# prog.net
KiCad netlist of a schematic drawn in EAGLE
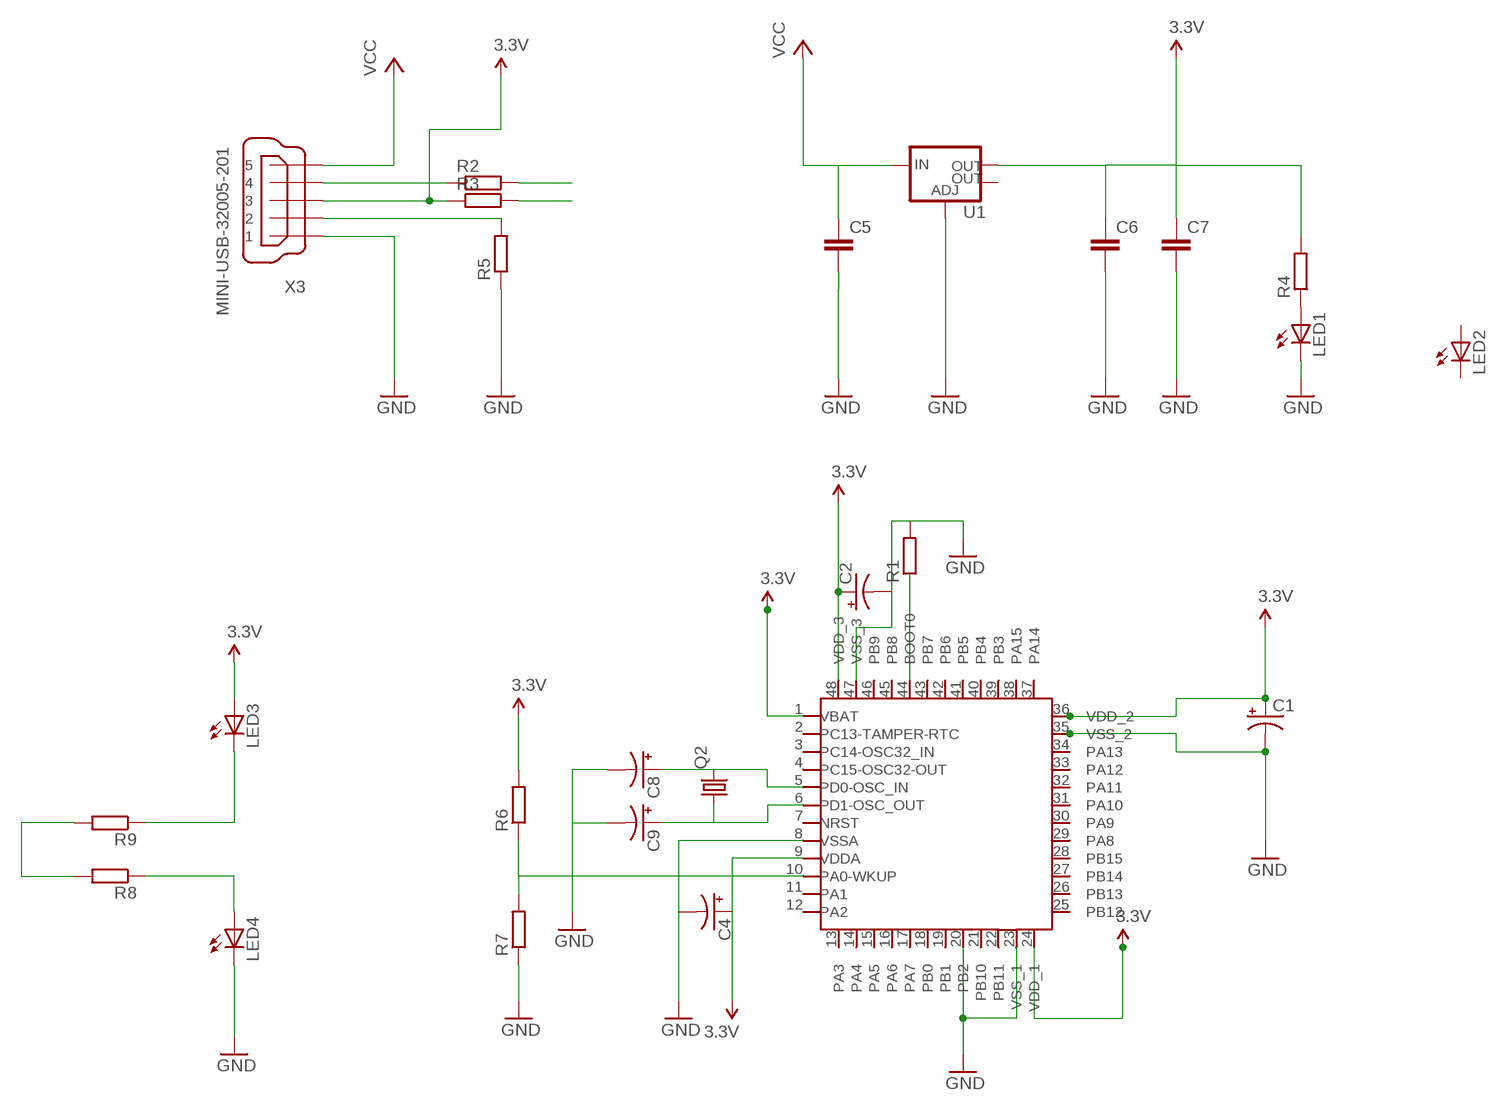
[diagram p0: schematic, sheet 1]

(export (version "E")
  (design (tool "Eeschema 10.0.6"))
  (components
    (comp (ref "C1")
      (value "POLARIZED_CAPACITORA3216-18")
      (footprint "eagle-import:A3216-18")
      (libsource (lib "eagle-import") (part "POLARIZED_CAPACITORA3216-18"))
    )
    (comp (ref "C2")
      (value "POLARIZED_CAPACITORA3216-18")
      (footprint "eagle-import:A3216-18")
      (libsource (lib "eagle-import") (part "POLARIZED_CAPACITORA3216-18"))
    )
    (comp (ref "C4")
      (value "POLARIZED_CAPACITORA3216-18")
      (footprint "eagle-import:A3216-18")
      (libsource (lib "eagle-import") (part "POLARIZED_CAPACITORA3216-18"))
    )
    (comp (ref "C5") (value "C") (footprint "eagle-import:C0805") (libsource (lib "eagle-import") (part "C")))
    (comp (ref "C6") (value "C") (footprint "eagle-import:C0805") (libsource (lib "eagle-import") (part "C")))
    (comp (ref "C7") (value "C") (footprint "eagle-import:C0805") (libsource (lib "eagle-import") (part "C")))
    (comp (ref "C8")
      (value "POLARIZED_CAPACITORA3216-18")
      (footprint "eagle-import:A3216-18")
      (libsource (lib "eagle-import") (part "POLARIZED_CAPACITORA3216-18"))
    )
    (comp (ref "C9")
      (value "POLARIZED_CAPACITORA3216-18")
      (footprint "eagle-import:A3216-18")
      (libsource (lib "eagle-import") (part "POLARIZED_CAPACITORA3216-18"))
    )
    (comp (ref "LED1")
      (value "LEDCHIP-LED0805")
      (footprint "eagle-import:CHIP-LED0805")
      (libsource (lib "eagle-import") (part "LEDCHIP-LED0805"))
    )
    (comp (ref "LED2")
      (value "LEDCHIP-LED0805")
      (footprint "eagle-import:CHIP-LED0805")
      (libsource (lib "eagle-import") (part "LEDCHIP-LED0805"))
    )
    (comp (ref "LED3")
      (value "LEDCHIP-LED0805")
      (footprint "eagle-import:CHIP-LED0805")
      (libsource (lib "eagle-import") (part "LEDCHIP-LED0805"))
    )
    (comp (ref "LED4")
      (value "LEDCHIP-LED0805")
      (footprint "eagle-import:CHIP-LED0805")
      (libsource (lib "eagle-import") (part "LEDCHIP-LED0805"))
    )
    (comp (ref "Q2")
      (value "CRYSTALSM49")
      (footprint "eagle-import:SM49")
      (libsource (lib "eagle-import") (part "CRYSTALSM49"))
    )
    (comp (ref "R1") (value "R") (footprint "eagle-import:R0805") (libsource (lib "eagle-import") (part "R")))
    (comp (ref "R2") (value "R") (footprint "eagle-import:R0805") (libsource (lib "eagle-import") (part "R")))
    (comp (ref "R3") (value "R") (footprint "eagle-import:R0805") (libsource (lib "eagle-import") (part "R")))
    (comp (ref "R4") (value "R") (footprint "eagle-import:R0805") (libsource (lib "eagle-import") (part "R")))
    (comp (ref "R5") (value "R") (footprint "eagle-import:R0805") (libsource (lib "eagle-import") (part "R")))
    (comp (ref "R6") (value "R") (footprint "eagle-import:R0805") (libsource (lib "eagle-import") (part "R")))
    (comp (ref "R7") (value "R") (footprint "eagle-import:R0805") (libsource (lib "eagle-import") (part "R")))
    (comp (ref "R8") (value "R") (footprint "eagle-import:R0805") (libsource (lib "eagle-import") (part "R")))
    (comp (ref "R9") (value "R") (footprint "eagle-import:R0805") (libsource (lib "eagle-import") (part "R")))
    (comp (ref "U$1")
      (value "STM32F103_TQFP48_7X7")
      (footprint "eagle-import:LQFP48_7X7")
      (libsource (lib "eagle-import") (part "STM32F103_TQFP48_7X7"))
    )
    (comp (ref "U1")
      (value "V_REG_LM1117SOT223")
      (footprint "eagle-import:SOT223")
      (libsource (lib "eagle-import") (part "V_REG_LM1117SOT223"))
    )
    (comp (ref "X3")
      (value "MINI-USB-32005-201")
      (footprint "eagle-import:32005-201")
      (libsource (lib "eagle-import") (part "MINI-USB-32005-201"))
    )
  )
  (nets
    (net (code "1") (name "3.3V") (class "Default")
      (node (ref "C1") (pin "+") (pinfunction "+_+") (pintype "passive"))
      (node (ref "C2") (pin "+") (pinfunction "+_+") (pintype "passive"))
      (node (ref "C4") (pin "+") (pinfunction "+_+") (pintype "passive"))
      (node (ref "C6") (pin "1") (pinfunction "1_1") (pintype "passive"))
      (node (ref "C7") (pin "1") (pinfunction "1_1") (pintype "passive"))
      (node (ref "LED3") (pin "A") (pinfunction "A_A") (pintype "passive"))
      (node (ref "R3") (pin "1") (pinfunction "1_1") (pintype "passive"))
      (node (ref "R4") (pin "2") (pinfunction "2_2") (pintype "passive"))
      (node (ref "R6") (pin "2") (pinfunction "2_2") (pintype "passive"))
      (node (ref "U$1") (pin "1") (pinfunction "VBAT_1") (pintype "bidirectional"))
      (node (ref "U$1") (pin "24") (pinfunction "VDD_1_24") (pintype "bidirectional"))
      (node (ref "U$1") (pin "36") (pinfunction "VDD_2_36") (pintype "bidirectional"))
      (node (ref "U$1") (pin "48") (pinfunction "VDD_3_48") (pintype "bidirectional"))
      (node (ref "U$1") (pin "9") (pinfunction "VDDA_9") (pintype "bidirectional"))
      (node (ref "U1") (pin "2") (pinfunction "OUT_2") (pintype "output"))
      (node (ref "X3") (pin "3") (pinfunction "3_3") (pintype "passive"))
    )
    (net (code "2") (name "GND") (class "Default")
      (node (ref "C1") (pin "-") (pinfunction "-_-") (pintype "passive"))
      (node (ref "C2") (pin "-") (pinfunction "-_-") (pintype "passive"))
      (node (ref "C4") (pin "-") (pinfunction "-_-") (pintype "passive"))
      (node (ref "C5") (pin "2") (pinfunction "2_2") (pintype "passive"))
      (node (ref "C6") (pin "2") (pinfunction "2_2") (pintype "passive"))
      (node (ref "C7") (pin "2") (pinfunction "2_2") (pintype "passive"))
      (node (ref "C8") (pin "-") (pinfunction "-_-") (pintype "passive"))
      (node (ref "C9") (pin "-") (pinfunction "-_-") (pintype "passive"))
      (node (ref "LED1") (pin "C") (pinfunction "C_C") (pintype "passive"))
      (node (ref "LED4") (pin "C") (pinfunction "C_C") (pintype "passive"))
      (node (ref "R1") (pin "2") (pinfunction "2_2") (pintype "passive"))
      (node (ref "R5") (pin "1") (pinfunction "1_1") (pintype "passive"))
      (node (ref "R7") (pin "1") (pinfunction "1_1") (pintype "passive"))
      (node (ref "U$1") (pin "20") (pinfunction "PB2_20") (pintype "bidirectional"))
      (node (ref "U$1") (pin "23") (pinfunction "VSS_1_23") (pintype "bidirectional"))
      (node (ref "U$1") (pin "35") (pinfunction "VSS_2_35") (pintype "bidirectional"))
      (node (ref "U$1") (pin "47") (pinfunction "VSS_3_47") (pintype "bidirectional"))
      (node (ref "U$1") (pin "8") (pinfunction "VSSA_8") (pintype "bidirectional"))
      (node (ref "U1") (pin "1") (pinfunction "ADJ_1") (pintype "input"))
      (node (ref "X3") (pin "1") (pinfunction "1_1") (pintype "passive"))
    )
    (net (code "3") (name "Net-(LED1-PadA)") (class "Default")
      (node (ref "LED1") (pin "A") (pinfunction "A_A") (pintype "passive"))
      (node (ref "R4") (pin "1") (pinfunction "1_1") (pintype "passive"))
    )
    (net (code "4") (name "Net-(LED3-PadC)") (class "Default")
      (node (ref "LED3") (pin "C") (pinfunction "C_C") (pintype "passive"))
      (node (ref "R9") (pin "1") (pinfunction "1_1") (pintype "passive"))
    )
    (net (code "5") (name "Net-(LED4-PadA)") (class "Default")
      (node (ref "LED4") (pin "A") (pinfunction "A_A") (pintype "passive"))
      (node (ref "R8") (pin "1") (pinfunction "1_1") (pintype "passive"))
    )
    (net (code "6") (name "Net-(R2-Pad1)") (class "Default")
      (node (ref "R2") (pin "1") (pinfunction "1_1") (pintype "passive"))
      (node (ref "X3") (pin "4") (pinfunction "4_4") (pintype "passive"))
    )
    (net (code "7") (name "Net-(R5-Pad2)") (class "Default")
      (node (ref "R5") (pin "2") (pinfunction "2_2") (pintype "passive"))
      (node (ref "X3") (pin "2") (pinfunction "2_2") (pintype "passive"))
    )
    (net (code "8") (name "Net-(R8-Pad2)") (class "Default")
      (node (ref "R8") (pin "2") (pinfunction "2_2") (pintype "passive"))
      (node (ref "R9") (pin "2") (pinfunction "2_2") (pintype "passive"))
    )
    (net (code "9") (name "Net-(U$1-BOOT0)") (class "Default")
      (node (ref "R1") (pin "1") (pinfunction "1_1") (pintype "passive"))
      (node (ref "U$1") (pin "44") (pinfunction "BOOT0_44") (pintype "bidirectional"))
    )
    (net (code "10") (name "Net-(U$1-PA0-WKUP)") (class "Default")
      (node (ref "R6") (pin "1") (pinfunction "1_1") (pintype "passive"))
      (node (ref "R7") (pin "2") (pinfunction "2_2") (pintype "passive"))
      (node (ref "U$1") (pin "10") (pinfunction "PA0-WKUP_10") (pintype "bidirectional"))
    )
    (net (code "11") (name "Net-(U$1-PD0-OSC_IN)") (class "Default")
      (node (ref "C8") (pin "+") (pinfunction "+_+") (pintype "passive"))
      (node (ref "Q2") (pin "2") (pinfunction "2_2") (pintype "passive"))
      (node (ref "U$1") (pin "5") (pinfunction "PD0-OSC_IN_5") (pintype "bidirectional"))
    )
    (net (code "12") (name "Net-(U$1-PD1-OSC_OUT)") (class "Default")
      (node (ref "C9") (pin "+") (pinfunction "+_+") (pintype "passive"))
      (node (ref "Q2") (pin "1") (pinfunction "1_1") (pintype "passive"))
      (node (ref "U$1") (pin "6") (pinfunction "PD1-OSC_OUT_6") (pintype "bidirectional"))
    )
    (net (code "13") (name "VCC") (class "Default")
      (node (ref "C5") (pin "1") (pinfunction "1_1") (pintype "passive"))
      (node (ref "U1") (pin "3") (pinfunction "IN_3") (pintype "input"))
      (node (ref "X3") (pin "5") (pinfunction "5_5") (pintype "passive"))
    )
    (net (code "14") (name "unconnected-(LED2-PadA)") (class "Default")
      (node (ref "LED2") (pin "A") (pinfunction "A_A") (pintype "passive"))
    )
    (net (code "15") (name "unconnected-(LED2-PadC)") (class "Default")
      (node (ref "LED2") (pin "C") (pinfunction "C_C") (pintype "passive"))
    )
    (net (code "16") (name "unconnected-(R2-Pad2)") (class "Default")
      (node (ref "R2") (pin "2") (pinfunction "2_2") (pintype "passive"))
    )
    (net (code "17") (name "unconnected-(R3-Pad2)") (class "Default")
      (node (ref "R3") (pin "2") (pinfunction "2_2") (pintype "passive"))
    )
    (net (code "18") (name "unconnected-(U$1-NRST-Pad7)") (class "Default")
      (node (ref "U$1") (pin "7") (pinfunction "NRST_7") (pintype "bidirectional"))
    )
    (net (code "19") (name "unconnected-(U$1-PA1-Pad11)") (class "Default")
      (node (ref "U$1") (pin "11") (pinfunction "PA1_11") (pintype "bidirectional"))
    )
    (net (code "20") (name "unconnected-(U$1-PA2-Pad12)") (class "Default")
      (node (ref "U$1") (pin "12") (pinfunction "PA2_12") (pintype "bidirectional"))
    )
    (net (code "21") (name "unconnected-(U$1-PA3-Pad13)") (class "Default")
      (node (ref "U$1") (pin "13") (pinfunction "PA3_13") (pintype "bidirectional"))
    )
    (net (code "22") (name "unconnected-(U$1-PA4-Pad14)") (class "Default")
      (node (ref "U$1") (pin "14") (pinfunction "PA4_14") (pintype "bidirectional"))
    )
    (net (code "23") (name "unconnected-(U$1-PA5-Pad15)") (class "Default")
      (node (ref "U$1") (pin "15") (pinfunction "PA5_15") (pintype "bidirectional"))
    )
    (net (code "24") (name "unconnected-(U$1-PA6-Pad16)") (class "Default")
      (node (ref "U$1") (pin "16") (pinfunction "PA6_16") (pintype "bidirectional"))
    )
    (net (code "25") (name "unconnected-(U$1-PA7-Pad17)") (class "Default")
      (node (ref "U$1") (pin "17") (pinfunction "PA7_17") (pintype "bidirectional"))
    )
    (net (code "26") (name "unconnected-(U$1-PA8-Pad29)") (class "Default")
      (node (ref "U$1") (pin "29") (pinfunction "PA8_29") (pintype "bidirectional"))
    )
    (net (code "27") (name "unconnected-(U$1-PA9-Pad30)") (class "Default")
      (node (ref "U$1") (pin "30") (pinfunction "PA9_30") (pintype "bidirectional"))
    )
    (net (code "28") (name "unconnected-(U$1-PA10-Pad31)") (class "Default")
      (node (ref "U$1") (pin "31") (pinfunction "PA10_31") (pintype "bidirectional"))
    )
    (net (code "29") (name "unconnected-(U$1-PA11-Pad32)") (class "Default")
      (node (ref "U$1") (pin "32") (pinfunction "PA11_32") (pintype "bidirectional"))
    )
    (net (code "30") (name "unconnected-(U$1-PA12-Pad33)") (class "Default")
      (node (ref "U$1") (pin "33") (pinfunction "PA12_33") (pintype "bidirectional"))
    )
    (net (code "31") (name "unconnected-(U$1-PA13-Pad34)") (class "Default")
      (node (ref "U$1") (pin "34") (pinfunction "PA13_34") (pintype "bidirectional"))
    )
    (net (code "32") (name "unconnected-(U$1-PA14-Pad37)") (class "Default")
      (node (ref "U$1") (pin "37") (pinfunction "PA14_37") (pintype "bidirectional"))
    )
    (net (code "33") (name "unconnected-(U$1-PA15-Pad38)") (class "Default")
      (node (ref "U$1") (pin "38") (pinfunction "PA15_38") (pintype "bidirectional"))
    )
    (net (code "34") (name "unconnected-(U$1-PB0-Pad18)") (class "Default")
      (node (ref "U$1") (pin "18") (pinfunction "PB0_18") (pintype "bidirectional"))
    )
    (net (code "35") (name "unconnected-(U$1-PB1-Pad19)") (class "Default")
      (node (ref "U$1") (pin "19") (pinfunction "PB1_19") (pintype "bidirectional"))
    )
    (net (code "36") (name "unconnected-(U$1-PB3-Pad39)") (class "Default")
      (node (ref "U$1") (pin "39") (pinfunction "PB3_39") (pintype "bidirectional"))
    )
    (net (code "37") (name "unconnected-(U$1-PB4-Pad40)") (class "Default")
      (node (ref "U$1") (pin "40") (pinfunction "PB4_40") (pintype "bidirectional"))
    )
    (net (code "38") (name "unconnected-(U$1-PB5-Pad41)") (class "Default")
      (node (ref "U$1") (pin "41") (pinfunction "PB5_41") (pintype "bidirectional"))
    )
    (net (code "39") (name "unconnected-(U$1-PB6-Pad42)") (class "Default")
      (node (ref "U$1") (pin "42") (pinfunction "PB6_42") (pintype "bidirectional"))
    )
    (net (code "40") (name "unconnected-(U$1-PB7-Pad43)") (class "Default")
      (node (ref "U$1") (pin "43") (pinfunction "PB7_43") (pintype "bidirectional"))
    )
    (net (code "41") (name "unconnected-(U$1-PB8-Pad45)") (class "Default")
      (node (ref "U$1") (pin "45") (pinfunction "PB8_45") (pintype "bidirectional"))
    )
    (net (code "42") (name "unconnected-(U$1-PB9-Pad46)") (class "Default")
      (node (ref "U$1") (pin "46") (pinfunction "PB9_46") (pintype "bidirectional"))
    )
    (net (code "43") (name "unconnected-(U$1-PB10-Pad21)") (class "Default")
      (node (ref "U$1") (pin "21") (pinfunction "PB10_21") (pintype "bidirectional"))
    )
    (net (code "44") (name "unconnected-(U$1-PB11-Pad22)") (class "Default")
      (node (ref "U$1") (pin "22") (pinfunction "PB11_22") (pintype "bidirectional"))
    )
    (net (code "45") (name "unconnected-(U$1-PB12-Pad25)") (class "Default")
      (node (ref "U$1") (pin "25") (pinfunction "PB12_25") (pintype "bidirectional"))
    )
    (net (code "46") (name "unconnected-(U$1-PB13-Pad26)") (class "Default")
      (node (ref "U$1") (pin "26") (pinfunction "PB13_26") (pintype "bidirectional"))
    )
    (net (code "47") (name "unconnected-(U$1-PB14-Pad27)") (class "Default")
      (node (ref "U$1") (pin "27") (pinfunction "PB14_27") (pintype "bidirectional"))
    )
    (net (code "48") (name "unconnected-(U$1-PB15-Pad28)") (class "Default")
      (node (ref "U$1") (pin "28") (pinfunction "PB15_28") (pintype "bidirectional"))
    )
    (net (code "49") (name "unconnected-(U$1-PC13-TAMPER-RTC-Pad2)") (class "Default")
      (node (ref "U$1") (pin "2") (pinfunction "PC13-TAMPER-RTC_2") (pintype "bidirectional"))
    )
    (net (code "50") (name "unconnected-(U$1-PC14-OSC32_IN-Pad3)") (class "Default")
      (node (ref "U$1") (pin "3") (pinfunction "PC14-OSC32_IN_3") (pintype "bidirectional"))
    )
    (net (code "51") (name "unconnected-(U$1-PC15-OSC32-OUT-Pad4)") (class "Default")
      (node (ref "U$1") (pin "4") (pinfunction "PC15-OSC32-OUT_4") (pintype "bidirectional"))
    )
    (net (code "52") (name "unconnected-(U1-OUT-Pad4)") (class "Default")
      (node (ref "U1") (pin "4") (pinfunction "OUT_4") (pintype "output"))
    )
  )
)
